# Register.net
KiCad netlist of a schematic drawn in EAGLE
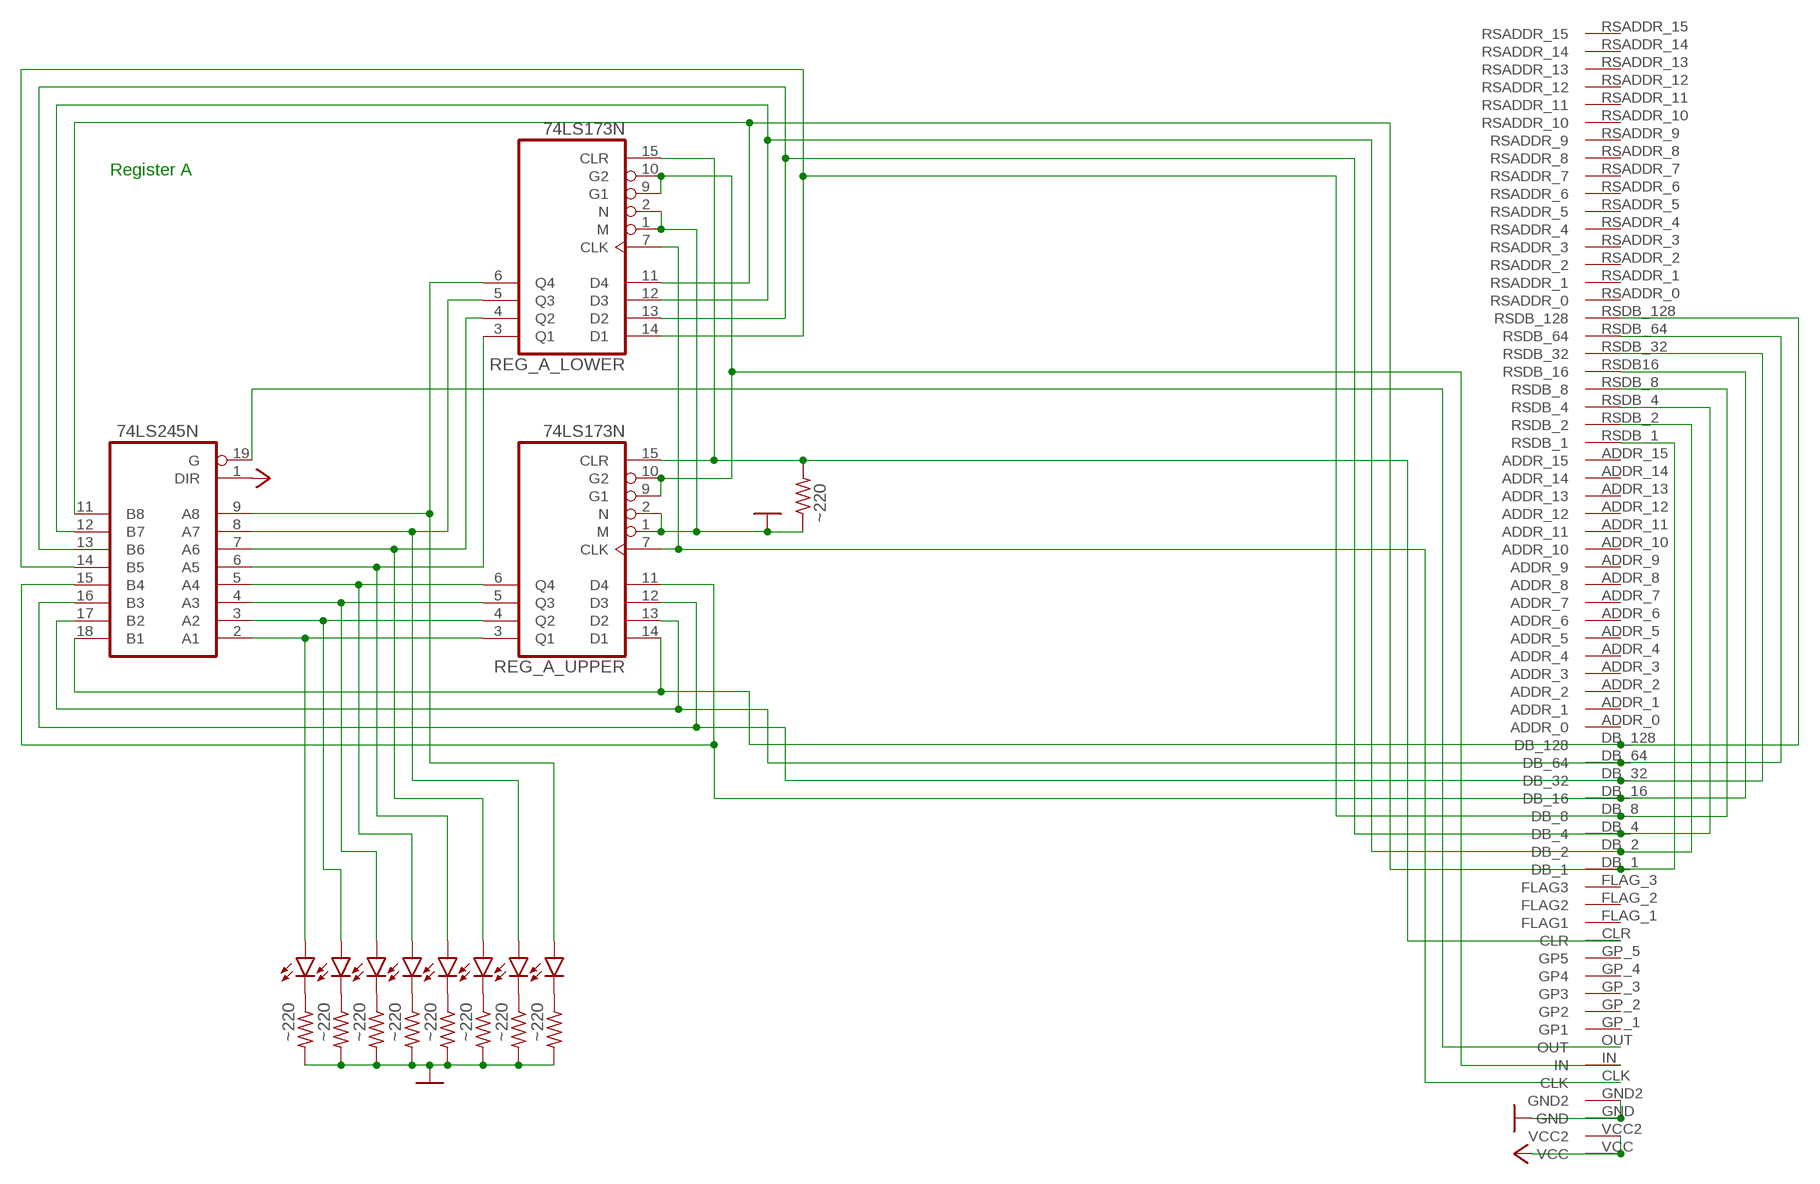
[diagram p0: schematic, sheet 1]

(export (version "E")
  (design (tool "Eeschema 10.0.6"))
  (components
    (comp (ref "LED_A_REG_1")
      (value "LED")
      (footprint "eagle-import:LED5MM")
      (libsource (lib "eagle-import") (part "LED5MM"))
    )
    (comp (ref "LED_A_REG_2")
      (value "LED")
      (footprint "eagle-import:LED5MM")
      (libsource (lib "eagle-import") (part "LED5MM"))
    )
    (comp (ref "LED_A_REG_3")
      (value "LED")
      (footprint "eagle-import:LED5MM")
      (libsource (lib "eagle-import") (part "LED5MM"))
    )
    (comp (ref "LED_A_REG_4")
      (value "LED")
      (footprint "eagle-import:LED5MM")
      (libsource (lib "eagle-import") (part "LED5MM"))
    )
    (comp (ref "LED_A_REG_5")
      (value "LED")
      (footprint "eagle-import:LED5MM")
      (libsource (lib "eagle-import") (part "LED5MM"))
    )
    (comp (ref "LED_A_REG_6")
      (value "LED")
      (footprint "eagle-import:LED5MM")
      (libsource (lib "eagle-import") (part "LED5MM"))
    )
    (comp (ref "LED_A_REG_7")
      (value "LED")
      (footprint "eagle-import:LED5MM")
      (libsource (lib "eagle-import") (part "LED5MM"))
    )
    (comp (ref "LED_A_REG_8")
      (value "LED")
      (footprint "eagle-import:LED5MM")
      (libsource (lib "eagle-import") (part "LED5MM"))
    )
    (comp (ref "OUTPUT_BUFFER_REG_A")
      (value "74LS245N")
      (footprint "eagle-import:DIL20")
      (libsource (lib "eagle-import") (part "74245NLS"))
    )
    (comp (ref "R1")
      (value "~220")
      (footprint "eagle-import:0204_7")
      (libsource (lib "eagle-import") (part "R-US_0204/7"))
    )
    (comp (ref "R2")
      (value "~220")
      (footprint "eagle-import:0204_7")
      (libsource (lib "eagle-import") (part "R-US_0204/7"))
    )
    (comp (ref "R3")
      (value "~220")
      (footprint "eagle-import:0204_7")
      (libsource (lib "eagle-import") (part "R-US_0204/7"))
    )
    (comp (ref "R4")
      (value "~220")
      (footprint "eagle-import:0204_7")
      (libsource (lib "eagle-import") (part "R-US_0204/7"))
    )
    (comp (ref "R5")
      (value "~220")
      (footprint "eagle-import:0204_7")
      (libsource (lib "eagle-import") (part "R-US_0204/7"))
    )
    (comp (ref "R6")
      (value "~220")
      (footprint "eagle-import:0204_7")
      (libsource (lib "eagle-import") (part "R-US_0204/7"))
    )
    (comp (ref "R7")
      (value "~220")
      (footprint "eagle-import:0204_7")
      (libsource (lib "eagle-import") (part "R-US_0204/7"))
    )
    (comp (ref "R8")
      (value "~220")
      (footprint "eagle-import:0204_7")
      (libsource (lib "eagle-import") (part "R-US_0204/7"))
    )
    (comp (ref "R9")
      (value "~220")
      (footprint "eagle-import:0204_7")
      (libsource (lib "eagle-import") (part "R-US_0204/7"))
    )
    (comp (ref "REG_A_LOWER")
      (value "74LS173N")
      (footprint "eagle-import:DIL16")
      (libsource (lib "eagle-import") (part "74173NLS"))
    )
    (comp (ref "REG_A_UPPER")
      (value "74LS173N")
      (footprint "eagle-import:DIL16")
      (libsource (lib "eagle-import") (part "74173NLS"))
    )
    (comp (ref "U$1")
      (value "BACKPLATE_INTERFACE")
      (footprint "eagle-import:EDGE_FOOTPRINT")
      (libsource (lib "eagle-import") (part "BACKPLATE_INTERFACE"))
    )
  )
  (nets
    (net (code "1") (name "GND") (class "Default")
      (node (ref "R1") (pin "2") (pinfunction "2_2") (pintype "passive"))
      (node (ref "R2") (pin "2") (pinfunction "2_2") (pintype "passive"))
      (node (ref "R3") (pin "2") (pinfunction "2_2") (pintype "passive"))
      (node (ref "R4") (pin "2") (pinfunction "2_2") (pintype "passive"))
      (node (ref "R5") (pin "2") (pinfunction "2_2") (pintype "passive"))
      (node (ref "R6") (pin "2") (pinfunction "2_2") (pintype "passive"))
      (node (ref "R7") (pin "2") (pinfunction "2_2") (pintype "passive"))
      (node (ref "R8") (pin "2") (pinfunction "2_2") (pintype "passive"))
      (node (ref "R9") (pin "1") (pinfunction "1_1") (pintype "passive"))
      (node (ref "REG_A_LOWER") (pin "1") (pinfunction "M_1") (pintype "input"))
      (node (ref "REG_A_LOWER") (pin "2") (pinfunction "N_2") (pintype "input"))
      (node (ref "REG_A_UPPER") (pin "1") (pinfunction "M_1") (pintype "input"))
      (node (ref "REG_A_UPPER") (pin "2") (pinfunction "N_2") (pintype "input"))
      (node (ref "U$1") (pin "GND") (pinfunction "GND_GND") (pintype "bidirectional"))
      (node (ref "U$1") (pin "GND2") (pinfunction "GND2_GND2") (pintype "bidirectional"))
    )
    (net (code "2") (name "Net-(LED_A_REG_1-C)") (class "Default")
      (node (ref "LED_A_REG_1") (pin "K") (pinfunction "C_K") (pintype "passive"))
      (node (ref "R1") (pin "1") (pinfunction "1_1") (pintype "passive"))
    )
    (net (code "3") (name "Net-(LED_A_REG_2-C)") (class "Default")
      (node (ref "LED_A_REG_2") (pin "K") (pinfunction "C_K") (pintype "passive"))
      (node (ref "R2") (pin "1") (pinfunction "1_1") (pintype "passive"))
    )
    (net (code "4") (name "Net-(LED_A_REG_3-C)") (class "Default")
      (node (ref "LED_A_REG_3") (pin "K") (pinfunction "C_K") (pintype "passive"))
      (node (ref "R3") (pin "1") (pinfunction "1_1") (pintype "passive"))
    )
    (net (code "5") (name "Net-(LED_A_REG_4-C)") (class "Default")
      (node (ref "LED_A_REG_4") (pin "K") (pinfunction "C_K") (pintype "passive"))
      (node (ref "R4") (pin "1") (pinfunction "1_1") (pintype "passive"))
    )
    (net (code "6") (name "Net-(LED_A_REG_5-C)") (class "Default")
      (node (ref "LED_A_REG_5") (pin "K") (pinfunction "C_K") (pintype "passive"))
      (node (ref "R5") (pin "1") (pinfunction "1_1") (pintype "passive"))
    )
    (net (code "7") (name "Net-(LED_A_REG_6-C)") (class "Default")
      (node (ref "LED_A_REG_6") (pin "K") (pinfunction "C_K") (pintype "passive"))
      (node (ref "R6") (pin "1") (pinfunction "1_1") (pintype "passive"))
    )
    (net (code "8") (name "Net-(LED_A_REG_7-C)") (class "Default")
      (node (ref "LED_A_REG_7") (pin "K") (pinfunction "C_K") (pintype "passive"))
      (node (ref "R7") (pin "1") (pinfunction "1_1") (pintype "passive"))
    )
    (net (code "9") (name "Net-(LED_A_REG_8-C)") (class "Default")
      (node (ref "LED_A_REG_8") (pin "K") (pinfunction "C_K") (pintype "passive"))
      (node (ref "R8") (pin "1") (pinfunction "1_1") (pintype "passive"))
    )
    (net (code "10") (name "Net-(OUTPUT_BUFFER_REG_AA-A1)") (class "Default")
      (node (ref "LED_A_REG_8") (pin "A") (pinfunction "A_A") (pintype "passive"))
      (node (ref "OUTPUT_BUFFER_REG_A") (pin "2") (pinfunction "A1_2") (pintype "bidirectional"))
      (node (ref "REG_A_UPPER") (pin "3") (pinfunction "Q1_3") (pintype "tri_state"))
    )
    (net (code "11") (name "Net-(OUTPUT_BUFFER_REG_AA-A2)") (class "Default")
      (node (ref "LED_A_REG_7") (pin "A") (pinfunction "A_A") (pintype "passive"))
      (node (ref "OUTPUT_BUFFER_REG_A") (pin "3") (pinfunction "A2_3") (pintype "bidirectional"))
      (node (ref "REG_A_UPPER") (pin "4") (pinfunction "Q2_4") (pintype "tri_state"))
    )
    (net (code "12") (name "Net-(OUTPUT_BUFFER_REG_AA-A3)") (class "Default")
      (node (ref "LED_A_REG_6") (pin "A") (pinfunction "A_A") (pintype "passive"))
      (node (ref "OUTPUT_BUFFER_REG_A") (pin "4") (pinfunction "A3_4") (pintype "bidirectional"))
      (node (ref "REG_A_UPPER") (pin "5") (pinfunction "Q3_5") (pintype "tri_state"))
    )
    (net (code "13") (name "Net-(OUTPUT_BUFFER_REG_AA-A4)") (class "Default")
      (node (ref "LED_A_REG_5") (pin "A") (pinfunction "A_A") (pintype "passive"))
      (node (ref "OUTPUT_BUFFER_REG_A") (pin "5") (pinfunction "A4_5") (pintype "bidirectional"))
      (node (ref "REG_A_UPPER") (pin "6") (pinfunction "Q4_6") (pintype "tri_state"))
    )
    (net (code "14") (name "Net-(OUTPUT_BUFFER_REG_AA-A5)") (class "Default")
      (node (ref "LED_A_REG_4") (pin "A") (pinfunction "A_A") (pintype "passive"))
      (node (ref "OUTPUT_BUFFER_REG_A") (pin "6") (pinfunction "A5_6") (pintype "bidirectional"))
      (node (ref "REG_A_LOWER") (pin "3") (pinfunction "Q1_3") (pintype "tri_state"))
    )
    (net (code "15") (name "Net-(OUTPUT_BUFFER_REG_AA-A6)") (class "Default")
      (node (ref "LED_A_REG_3") (pin "A") (pinfunction "A_A") (pintype "passive"))
      (node (ref "OUTPUT_BUFFER_REG_A") (pin "7") (pinfunction "A6_7") (pintype "bidirectional"))
      (node (ref "REG_A_LOWER") (pin "4") (pinfunction "Q2_4") (pintype "tri_state"))
    )
    (net (code "16") (name "Net-(OUTPUT_BUFFER_REG_AA-A7)") (class "Default")
      (node (ref "LED_A_REG_2") (pin "A") (pinfunction "A_A") (pintype "passive"))
      (node (ref "OUTPUT_BUFFER_REG_A") (pin "8") (pinfunction "A7_8") (pintype "bidirectional"))
      (node (ref "REG_A_LOWER") (pin "5") (pinfunction "Q3_5") (pintype "tri_state"))
    )
    (net (code "17") (name "Net-(OUTPUT_BUFFER_REG_AA-A8)") (class "Default")
      (node (ref "LED_A_REG_1") (pin "A") (pinfunction "A_A") (pintype "passive"))
      (node (ref "OUTPUT_BUFFER_REG_A") (pin "9") (pinfunction "A8_9") (pintype "bidirectional"))
      (node (ref "REG_A_LOWER") (pin "6") (pinfunction "Q4_6") (pintype "tri_state"))
    )
    (net (code "18") (name "Net-(OUTPUT_BUFFER_REG_AA-B1)") (class "Default")
      (node (ref "OUTPUT_BUFFER_REG_A") (pin "18") (pinfunction "B1_18") (pintype "bidirectional"))
      (node (ref "REG_A_UPPER") (pin "14") (pinfunction "D1_14") (pintype "input"))
      (node (ref "U$1") (pin "DB_128") (pinfunction "DB_128_DB_128") (pintype "bidirectional"))
      (node (ref "U$1") (pin "RSDB_128") (pinfunction "RSDB_128_RSDB_128") (pintype "bidirectional"))
    )
    (net (code "19") (name "Net-(OUTPUT_BUFFER_REG_AA-B2)") (class "Default")
      (node (ref "OUTPUT_BUFFER_REG_A") (pin "17") (pinfunction "B2_17") (pintype "bidirectional"))
      (node (ref "REG_A_UPPER") (pin "13") (pinfunction "D2_13") (pintype "input"))
      (node (ref "U$1") (pin "DB_64") (pinfunction "DB_64_DB_64") (pintype "bidirectional"))
      (node (ref "U$1") (pin "RSDB_64") (pinfunction "RSDB_64_RSDB_64") (pintype "bidirectional"))
    )
    (net (code "20") (name "Net-(OUTPUT_BUFFER_REG_AA-B3)") (class "Default")
      (node (ref "OUTPUT_BUFFER_REG_A") (pin "16") (pinfunction "B3_16") (pintype "bidirectional"))
      (node (ref "REG_A_UPPER") (pin "12") (pinfunction "D3_12") (pintype "input"))
      (node (ref "U$1") (pin "DB_32") (pinfunction "DB_32_DB_32") (pintype "bidirectional"))
      (node (ref "U$1") (pin "RSDB_32") (pinfunction "RSDB_32_RSDB_32") (pintype "bidirectional"))
    )
    (net (code "21") (name "Net-(OUTPUT_BUFFER_REG_AA-B4)") (class "Default")
      (node (ref "OUTPUT_BUFFER_REG_A") (pin "15") (pinfunction "B4_15") (pintype "bidirectional"))
      (node (ref "REG_A_UPPER") (pin "11") (pinfunction "D4_11") (pintype "input"))
      (node (ref "U$1") (pin "DB_16") (pinfunction "DB_16_DB_16") (pintype "bidirectional"))
      (node (ref "U$1") (pin "RSDB16") (pinfunction "RSDB_16_RSDB16") (pintype "bidirectional"))
    )
    (net (code "22") (name "Net-(OUTPUT_BUFFER_REG_AA-B5)") (class "Default")
      (node (ref "OUTPUT_BUFFER_REG_A") (pin "14") (pinfunction "B5_14") (pintype "bidirectional"))
      (node (ref "REG_A_LOWER") (pin "14") (pinfunction "D1_14") (pintype "input"))
      (node (ref "U$1") (pin "DB_8") (pinfunction "DB_8_DB_8") (pintype "bidirectional"))
      (node (ref "U$1") (pin "RSDB_8") (pinfunction "RSDB_8_RSDB_8") (pintype "bidirectional"))
    )
    (net (code "23") (name "Net-(OUTPUT_BUFFER_REG_AA-B6)") (class "Default")
      (node (ref "OUTPUT_BUFFER_REG_A") (pin "13") (pinfunction "B6_13") (pintype "bidirectional"))
      (node (ref "REG_A_LOWER") (pin "13") (pinfunction "D2_13") (pintype "input"))
      (node (ref "U$1") (pin "DB_4") (pinfunction "DB_4_DB_4") (pintype "bidirectional"))
      (node (ref "U$1") (pin "RSDB_4") (pinfunction "RSDB_4_RSDB_4") (pintype "bidirectional"))
    )
    (net (code "24") (name "Net-(OUTPUT_BUFFER_REG_AA-B7)") (class "Default")
      (node (ref "OUTPUT_BUFFER_REG_A") (pin "12") (pinfunction "B7_12") (pintype "bidirectional"))
      (node (ref "REG_A_LOWER") (pin "12") (pinfunction "D3_12") (pintype "input"))
      (node (ref "U$1") (pin "DB_2") (pinfunction "DB_2_DB_2") (pintype "bidirectional"))
      (node (ref "U$1") (pin "RSDB_2") (pinfunction "RSDB_2_RSDB_2") (pintype "bidirectional"))
    )
    (net (code "25") (name "Net-(OUTPUT_BUFFER_REG_AA-B8)") (class "Default")
      (node (ref "OUTPUT_BUFFER_REG_A") (pin "11") (pinfunction "B8_11") (pintype "bidirectional"))
      (node (ref "REG_A_LOWER") (pin "11") (pinfunction "D4_11") (pintype "input"))
      (node (ref "U$1") (pin "DB_1") (pinfunction "DB_1_DB_1") (pintype "bidirectional"))
      (node (ref "U$1") (pin "RSDB_1") (pinfunction "RSDB_1_RSDB_1") (pintype "bidirectional"))
    )
    (net (code "26") (name "Net-(OUTPUT_BUFFER_REG_AA-G)") (class "Default")
      (node (ref "OUTPUT_BUFFER_REG_A") (pin "19") (pinfunction "G_19") (pintype "input"))
      (node (ref "U$1") (pin "OUT") (pinfunction "OUT_OUT") (pintype "bidirectional"))
    )
    (net (code "27") (name "Net-(REG_A_LOWERA-CLK)") (class "Default")
      (node (ref "REG_A_LOWER") (pin "7") (pinfunction "CLK_7") (pintype "input"))
      (node (ref "REG_A_UPPER") (pin "7") (pinfunction "CLK_7") (pintype "input"))
      (node (ref "U$1") (pin "CLK") (pinfunction "CLK_CLK") (pintype "bidirectional"))
    )
    (net (code "28") (name "Net-(REG_A_LOWERA-CLR)") (class "Default")
      (node (ref "R9") (pin "2") (pinfunction "2_2") (pintype "passive"))
      (node (ref "REG_A_LOWER") (pin "15") (pinfunction "CLR_15") (pintype "input"))
      (node (ref "REG_A_UPPER") (pin "15") (pinfunction "CLR_15") (pintype "input"))
      (node (ref "U$1") (pin "CLR") (pinfunction "CLR_CLR") (pintype "bidirectional"))
    )
    (net (code "29") (name "Net-(REG_A_LOWERA-G1)") (class "Default")
      (node (ref "REG_A_LOWER") (pin "10") (pinfunction "G2_10") (pintype "input"))
      (node (ref "REG_A_LOWER") (pin "9") (pinfunction "G1_9") (pintype "input"))
      (node (ref "REG_A_UPPER") (pin "10") (pinfunction "G2_10") (pintype "input"))
      (node (ref "REG_A_UPPER") (pin "9") (pinfunction "G1_9") (pintype "input"))
      (node (ref "U$1") (pin "IN") (pinfunction "IN_IN") (pintype "bidirectional"))
    )
    (net (code "30") (name "VCC") (class "Default")
      (node (ref "OUTPUT_BUFFER_REG_A") (pin "1") (pinfunction "DIR_1") (pintype "input"))
      (node (ref "U$1") (pin "VCC") (pinfunction "VCC_VCC") (pintype "bidirectional"))
      (node (ref "U$1") (pin "VCC2") (pinfunction "VCC2_VCC2") (pintype "bidirectional"))
    )
    (net (code "31") (name "unconnected-(U$1-FLAG1-PadFLAG_1)") (class "Default")
      (node (ref "U$1") (pin "FLAG_1") (pinfunction "FLAG1_FLAG_1") (pintype "bidirectional"))
    )
    (net (code "32") (name "unconnected-(U$1-FLAG2-PadFLAG_2)") (class "Default")
      (node (ref "U$1") (pin "FLAG_2") (pinfunction "FLAG2_FLAG_2") (pintype "bidirectional"))
    )
    (net (code "33") (name "unconnected-(U$1-FLAG3-PadFLAG_3)") (class "Default")
      (node (ref "U$1") (pin "FLAG_3") (pinfunction "FLAG3_FLAG_3") (pintype "bidirectional"))
    )
    (net (code "34") (name "unconnected-(U$1-GP1-PadGP_1)") (class "Default")
      (node (ref "U$1") (pin "GP_1") (pinfunction "GP1_GP_1") (pintype "bidirectional"))
    )
    (net (code "35") (name "unconnected-(U$1-GP2-PadGP_2)") (class "Default")
      (node (ref "U$1") (pin "GP_2") (pinfunction "GP2_GP_2") (pintype "bidirectional"))
    )
    (net (code "36") (name "unconnected-(U$1-GP3-PadGP_3)") (class "Default")
      (node (ref "U$1") (pin "GP_3") (pinfunction "GP3_GP_3") (pintype "bidirectional"))
    )
    (net (code "37") (name "unconnected-(U$1-GP4-PadGP_4)") (class "Default")
      (node (ref "U$1") (pin "GP_4") (pinfunction "GP4_GP_4") (pintype "bidirectional"))
    )
    (net (code "38") (name "unconnected-(U$1-GP5-PadGP_5)") (class "Default")
      (node (ref "U$1") (pin "GP_5") (pinfunction "GP5_GP_5") (pintype "bidirectional"))
    )
    (net (code "39") (name "unconnected-(U$1-PadADDR_0)") (class "Default")
      (node (ref "U$1") (pin "ADDR_0") (pinfunction "ADDR_0_ADDR_0") (pintype "bidirectional"))
    )
    (net (code "40") (name "unconnected-(U$1-PadADDR_1)") (class "Default")
      (node (ref "U$1") (pin "ADDR_1") (pinfunction "ADDR_1_ADDR_1") (pintype "bidirectional"))
    )
    (net (code "41") (name "unconnected-(U$1-PadADDR_2)") (class "Default")
      (node (ref "U$1") (pin "ADDR_2") (pinfunction "ADDR_2_ADDR_2") (pintype "bidirectional"))
    )
    (net (code "42") (name "unconnected-(U$1-PadADDR_3)") (class "Default")
      (node (ref "U$1") (pin "ADDR_3") (pinfunction "ADDR_3_ADDR_3") (pintype "bidirectional"))
    )
    (net (code "43") (name "unconnected-(U$1-PadADDR_4)") (class "Default")
      (node (ref "U$1") (pin "ADDR_4") (pinfunction "ADDR_4_ADDR_4") (pintype "bidirectional"))
    )
    (net (code "44") (name "unconnected-(U$1-PadADDR_5)") (class "Default")
      (node (ref "U$1") (pin "ADDR_5") (pinfunction "ADDR_5_ADDR_5") (pintype "bidirectional"))
    )
    (net (code "45") (name "unconnected-(U$1-PadADDR_6)") (class "Default")
      (node (ref "U$1") (pin "ADDR_6") (pinfunction "ADDR_6_ADDR_6") (pintype "bidirectional"))
    )
    (net (code "46") (name "unconnected-(U$1-PadADDR_7)") (class "Default")
      (node (ref "U$1") (pin "ADDR_7") (pinfunction "ADDR_7_ADDR_7") (pintype "bidirectional"))
    )
    (net (code "47") (name "unconnected-(U$1-PadADDR_8)") (class "Default")
      (node (ref "U$1") (pin "ADDR_8") (pinfunction "ADDR_8_ADDR_8") (pintype "bidirectional"))
    )
    (net (code "48") (name "unconnected-(U$1-PadADDR_9)") (class "Default")
      (node (ref "U$1") (pin "ADDR_9") (pinfunction "ADDR_9_ADDR_9") (pintype "bidirectional"))
    )
    (net (code "49") (name "unconnected-(U$1-PadADDR_10)") (class "Default")
      (node (ref "U$1") (pin "ADDR_10") (pinfunction "ADDR_10_ADDR_10") (pintype "bidirectional"))
    )
    (net (code "50") (name "unconnected-(U$1-PadADDR_11)") (class "Default")
      (node (ref "U$1") (pin "ADDR_11") (pinfunction "ADDR_11_ADDR_11") (pintype "bidirectional"))
    )
    (net (code "51") (name "unconnected-(U$1-PadADDR_12)") (class "Default")
      (node (ref "U$1") (pin "ADDR_12") (pinfunction "ADDR_12_ADDR_12") (pintype "bidirectional"))
    )
    (net (code "52") (name "unconnected-(U$1-PadADDR_13)") (class "Default")
      (node (ref "U$1") (pin "ADDR_13") (pinfunction "ADDR_13_ADDR_13") (pintype "bidirectional"))
    )
    (net (code "53") (name "unconnected-(U$1-PadADDR_14)") (class "Default")
      (node (ref "U$1") (pin "ADDR_14") (pinfunction "ADDR_14_ADDR_14") (pintype "bidirectional"))
    )
    (net (code "54") (name "unconnected-(U$1-PadADDR_15)") (class "Default")
      (node (ref "U$1") (pin "ADDR_15") (pinfunction "ADDR_15_ADDR_15") (pintype "bidirectional"))
    )
    (net (code "55") (name "unconnected-(U$1-PadRSADDR_0)") (class "Default")
      (node (ref "U$1") (pin "RSADDR_0") (pinfunction "RSADDR_0_RSADDR_0") (pintype "bidirectional"))
    )
    (net (code "56") (name "unconnected-(U$1-PadRSADDR_1)") (class "Default")
      (node (ref "U$1") (pin "RSADDR_1") (pinfunction "RSADDR_1_RSADDR_1") (pintype "bidirectional"))
    )
    (net (code "57") (name "unconnected-(U$1-PadRSADDR_2)") (class "Default")
      (node (ref "U$1") (pin "RSADDR_2") (pinfunction "RSADDR_2_RSADDR_2") (pintype "bidirectional"))
    )
    (net (code "58") (name "unconnected-(U$1-PadRSADDR_3)") (class "Default")
      (node (ref "U$1") (pin "RSADDR_3") (pinfunction "RSADDR_3_RSADDR_3") (pintype "bidirectional"))
    )
    (net (code "59") (name "unconnected-(U$1-PadRSADDR_4)") (class "Default")
      (node (ref "U$1") (pin "RSADDR_4") (pinfunction "RSADDR_4_RSADDR_4") (pintype "bidirectional"))
    )
    (net (code "60") (name "unconnected-(U$1-PadRSADDR_5)") (class "Default")
      (node (ref "U$1") (pin "RSADDR_5") (pinfunction "RSADDR_5_RSADDR_5") (pintype "bidirectional"))
    )
    (net (code "61") (name "unconnected-(U$1-PadRSADDR_6)") (class "Default")
      (node (ref "U$1") (pin "RSADDR_6") (pinfunction "RSADDR_6_RSADDR_6") (pintype "bidirectional"))
    )
    (net (code "62") (name "unconnected-(U$1-PadRSADDR_7)") (class "Default")
      (node (ref "U$1") (pin "RSADDR_7") (pinfunction "RSADDR_7_RSADDR_7") (pintype "bidirectional"))
    )
    (net (code "63") (name "unconnected-(U$1-PadRSADDR_8)") (class "Default")
      (node (ref "U$1") (pin "RSADDR_8") (pinfunction "RSADDR_8_RSADDR_8") (pintype "bidirectional"))
    )
    (net (code "64") (name "unconnected-(U$1-PadRSADDR_9)") (class "Default")
      (node (ref "U$1") (pin "RSADDR_9") (pinfunction "RSADDR_9_RSADDR_9") (pintype "bidirectional"))
    )
    (net (code "65") (name "unconnected-(U$1-PadRSADDR_10)") (class "Default")
      (node (ref "U$1") (pin "RSADDR_10") (pinfunction "RSADDR_10_RSADDR_10") (pintype "bidirectional"))
    )
    (net (code "66") (name "unconnected-(U$1-PadRSADDR_11)") (class "Default")
      (node (ref "U$1") (pin "RSADDR_11") (pinfunction "RSADDR_11_RSADDR_11") (pintype "bidirectional"))
    )
    (net (code "67") (name "unconnected-(U$1-PadRSADDR_12)") (class "Default")
      (node (ref "U$1") (pin "RSADDR_12") (pinfunction "RSADDR_12_RSADDR_12") (pintype "bidirectional"))
    )
    (net (code "68") (name "unconnected-(U$1-PadRSADDR_13)") (class "Default")
      (node (ref "U$1") (pin "RSADDR_13") (pinfunction "RSADDR_13_RSADDR_13") (pintype "bidirectional"))
    )
    (net (code "69") (name "unconnected-(U$1-PadRSADDR_14)") (class "Default")
      (node (ref "U$1") (pin "RSADDR_14") (pinfunction "RSADDR_14_RSADDR_14") (pintype "bidirectional"))
    )
    (net (code "70") (name "unconnected-(U$1-PadRSADDR_15)") (class "Default")
      (node (ref "U$1") (pin "RSADDR_15") (pinfunction "RSADDR_15_RSADDR_15") (pintype "bidirectional"))
    )
  )
)
